# EasyEda_SCH_CAD-Mouse_2025-05-26.net
KiCad netlist of a schematic drawn in EasyEDA
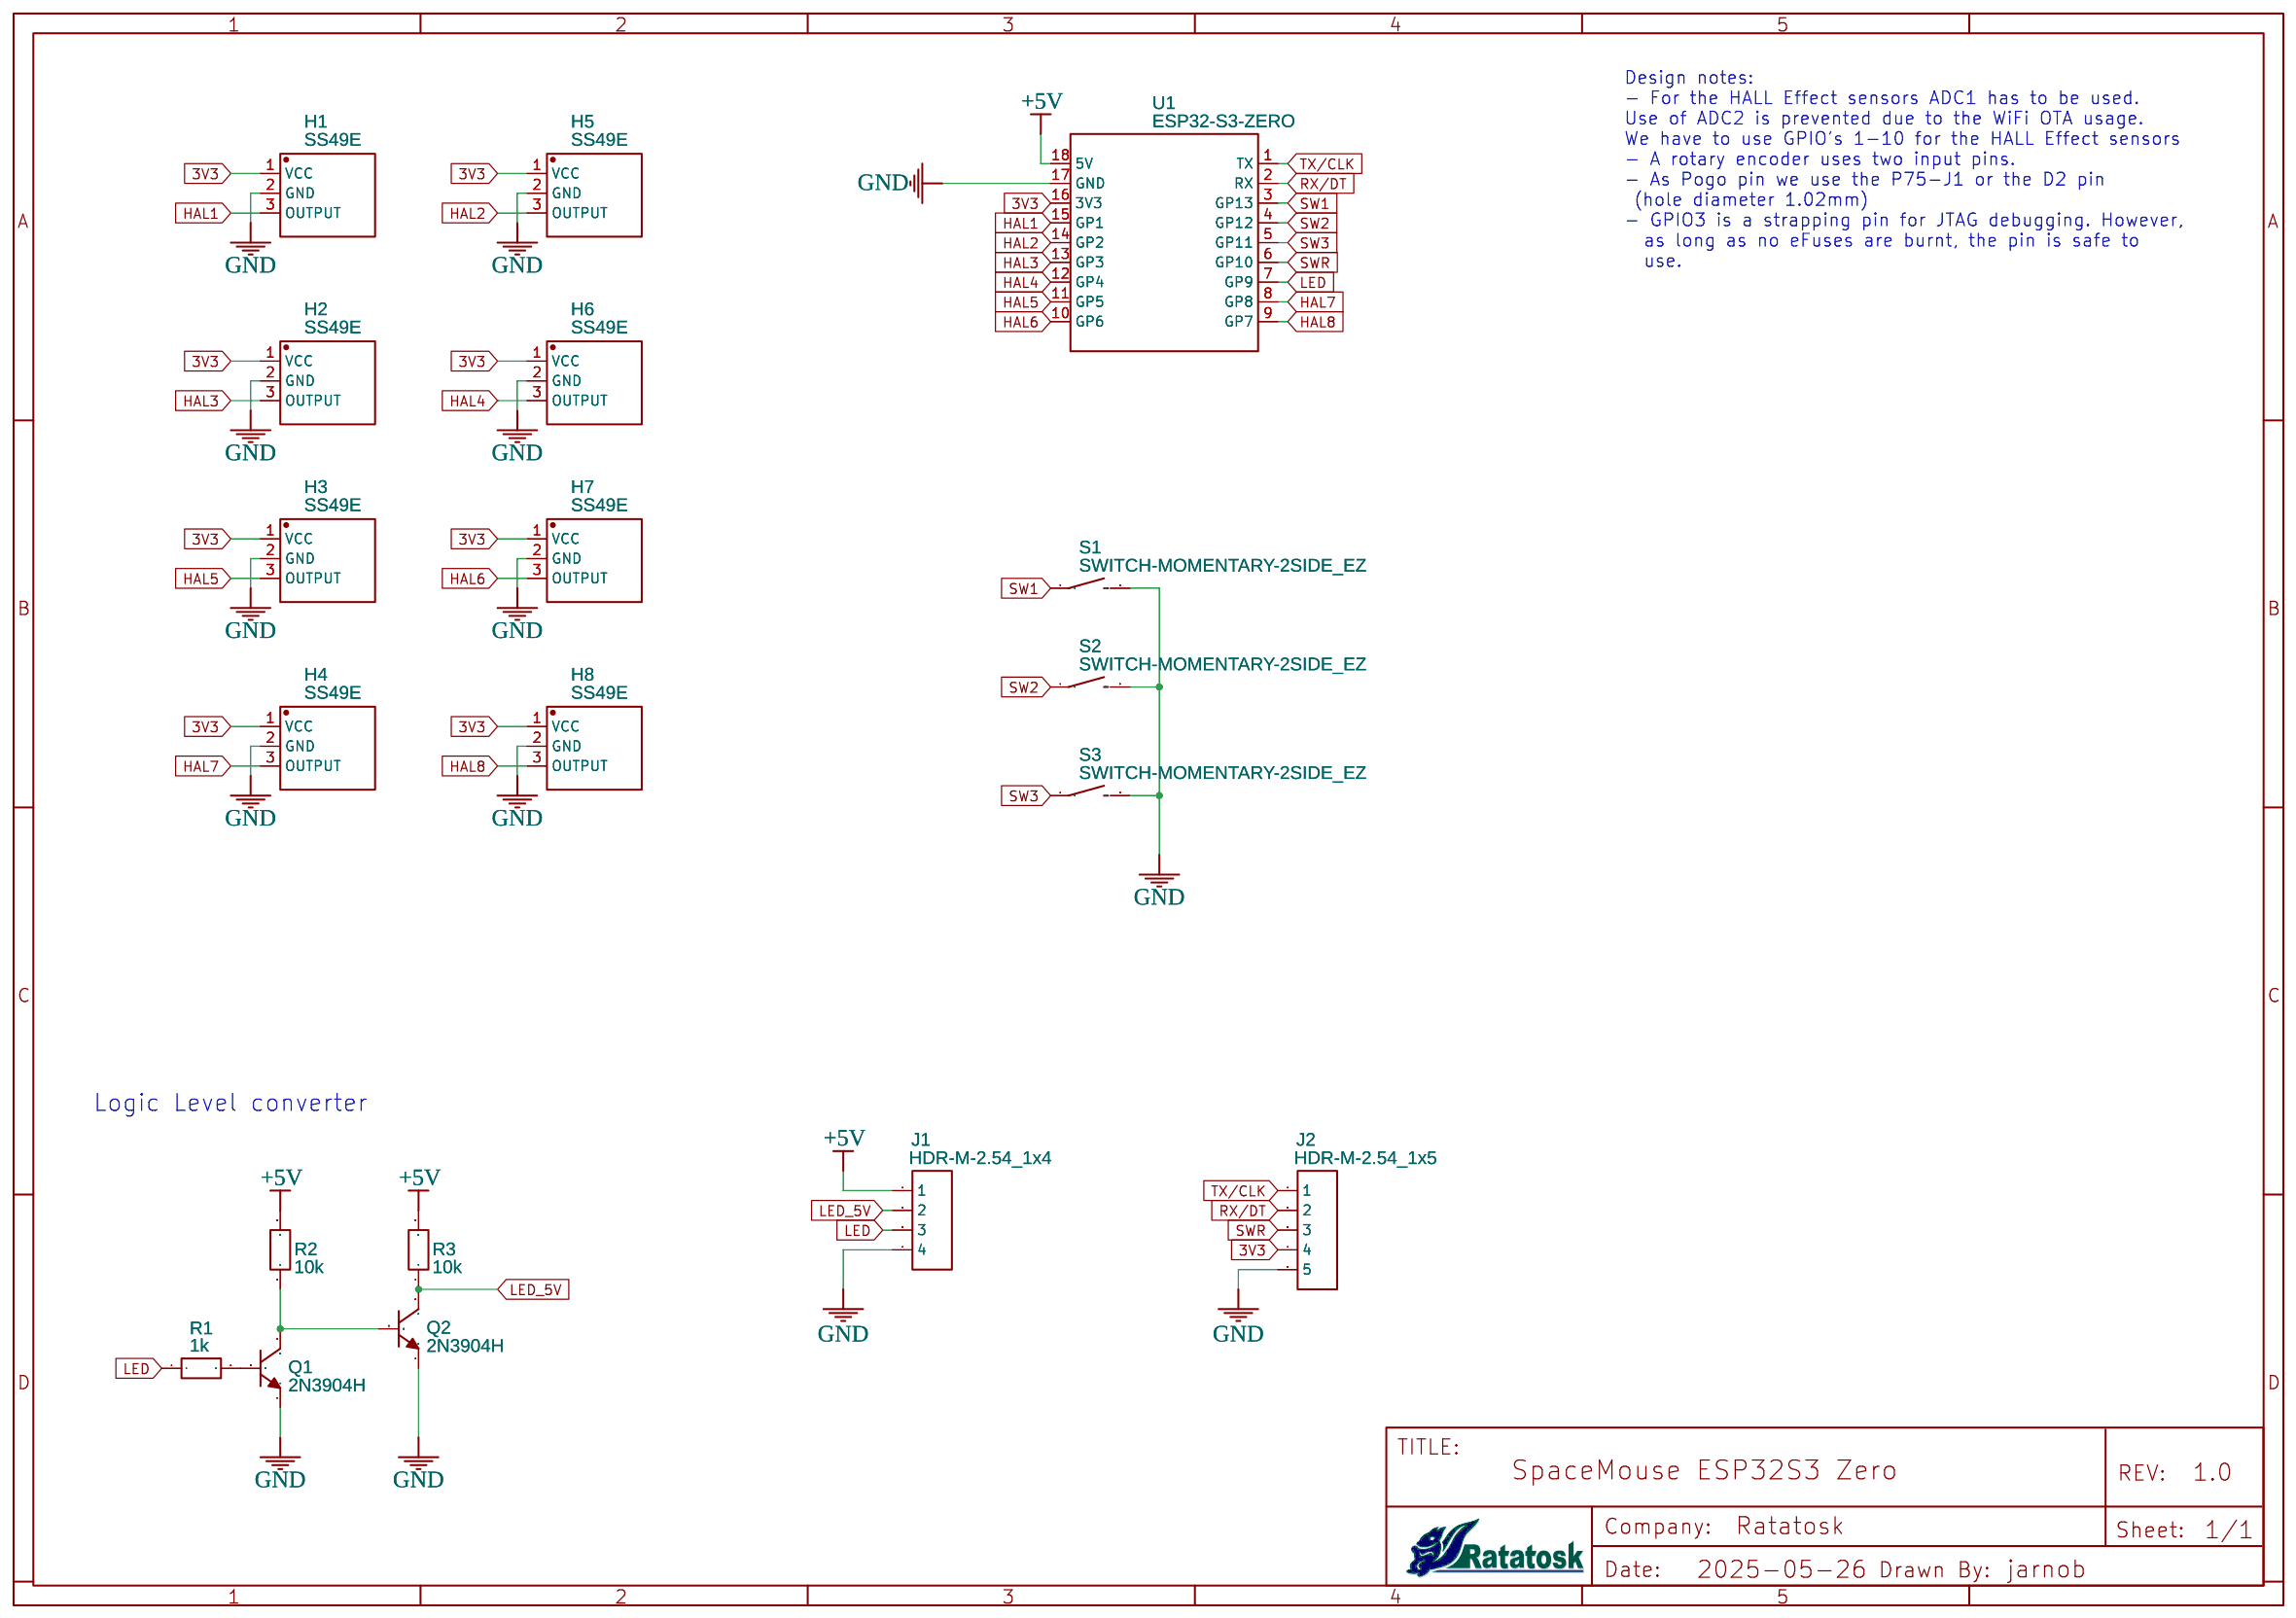
[diagram p0: Schematic]
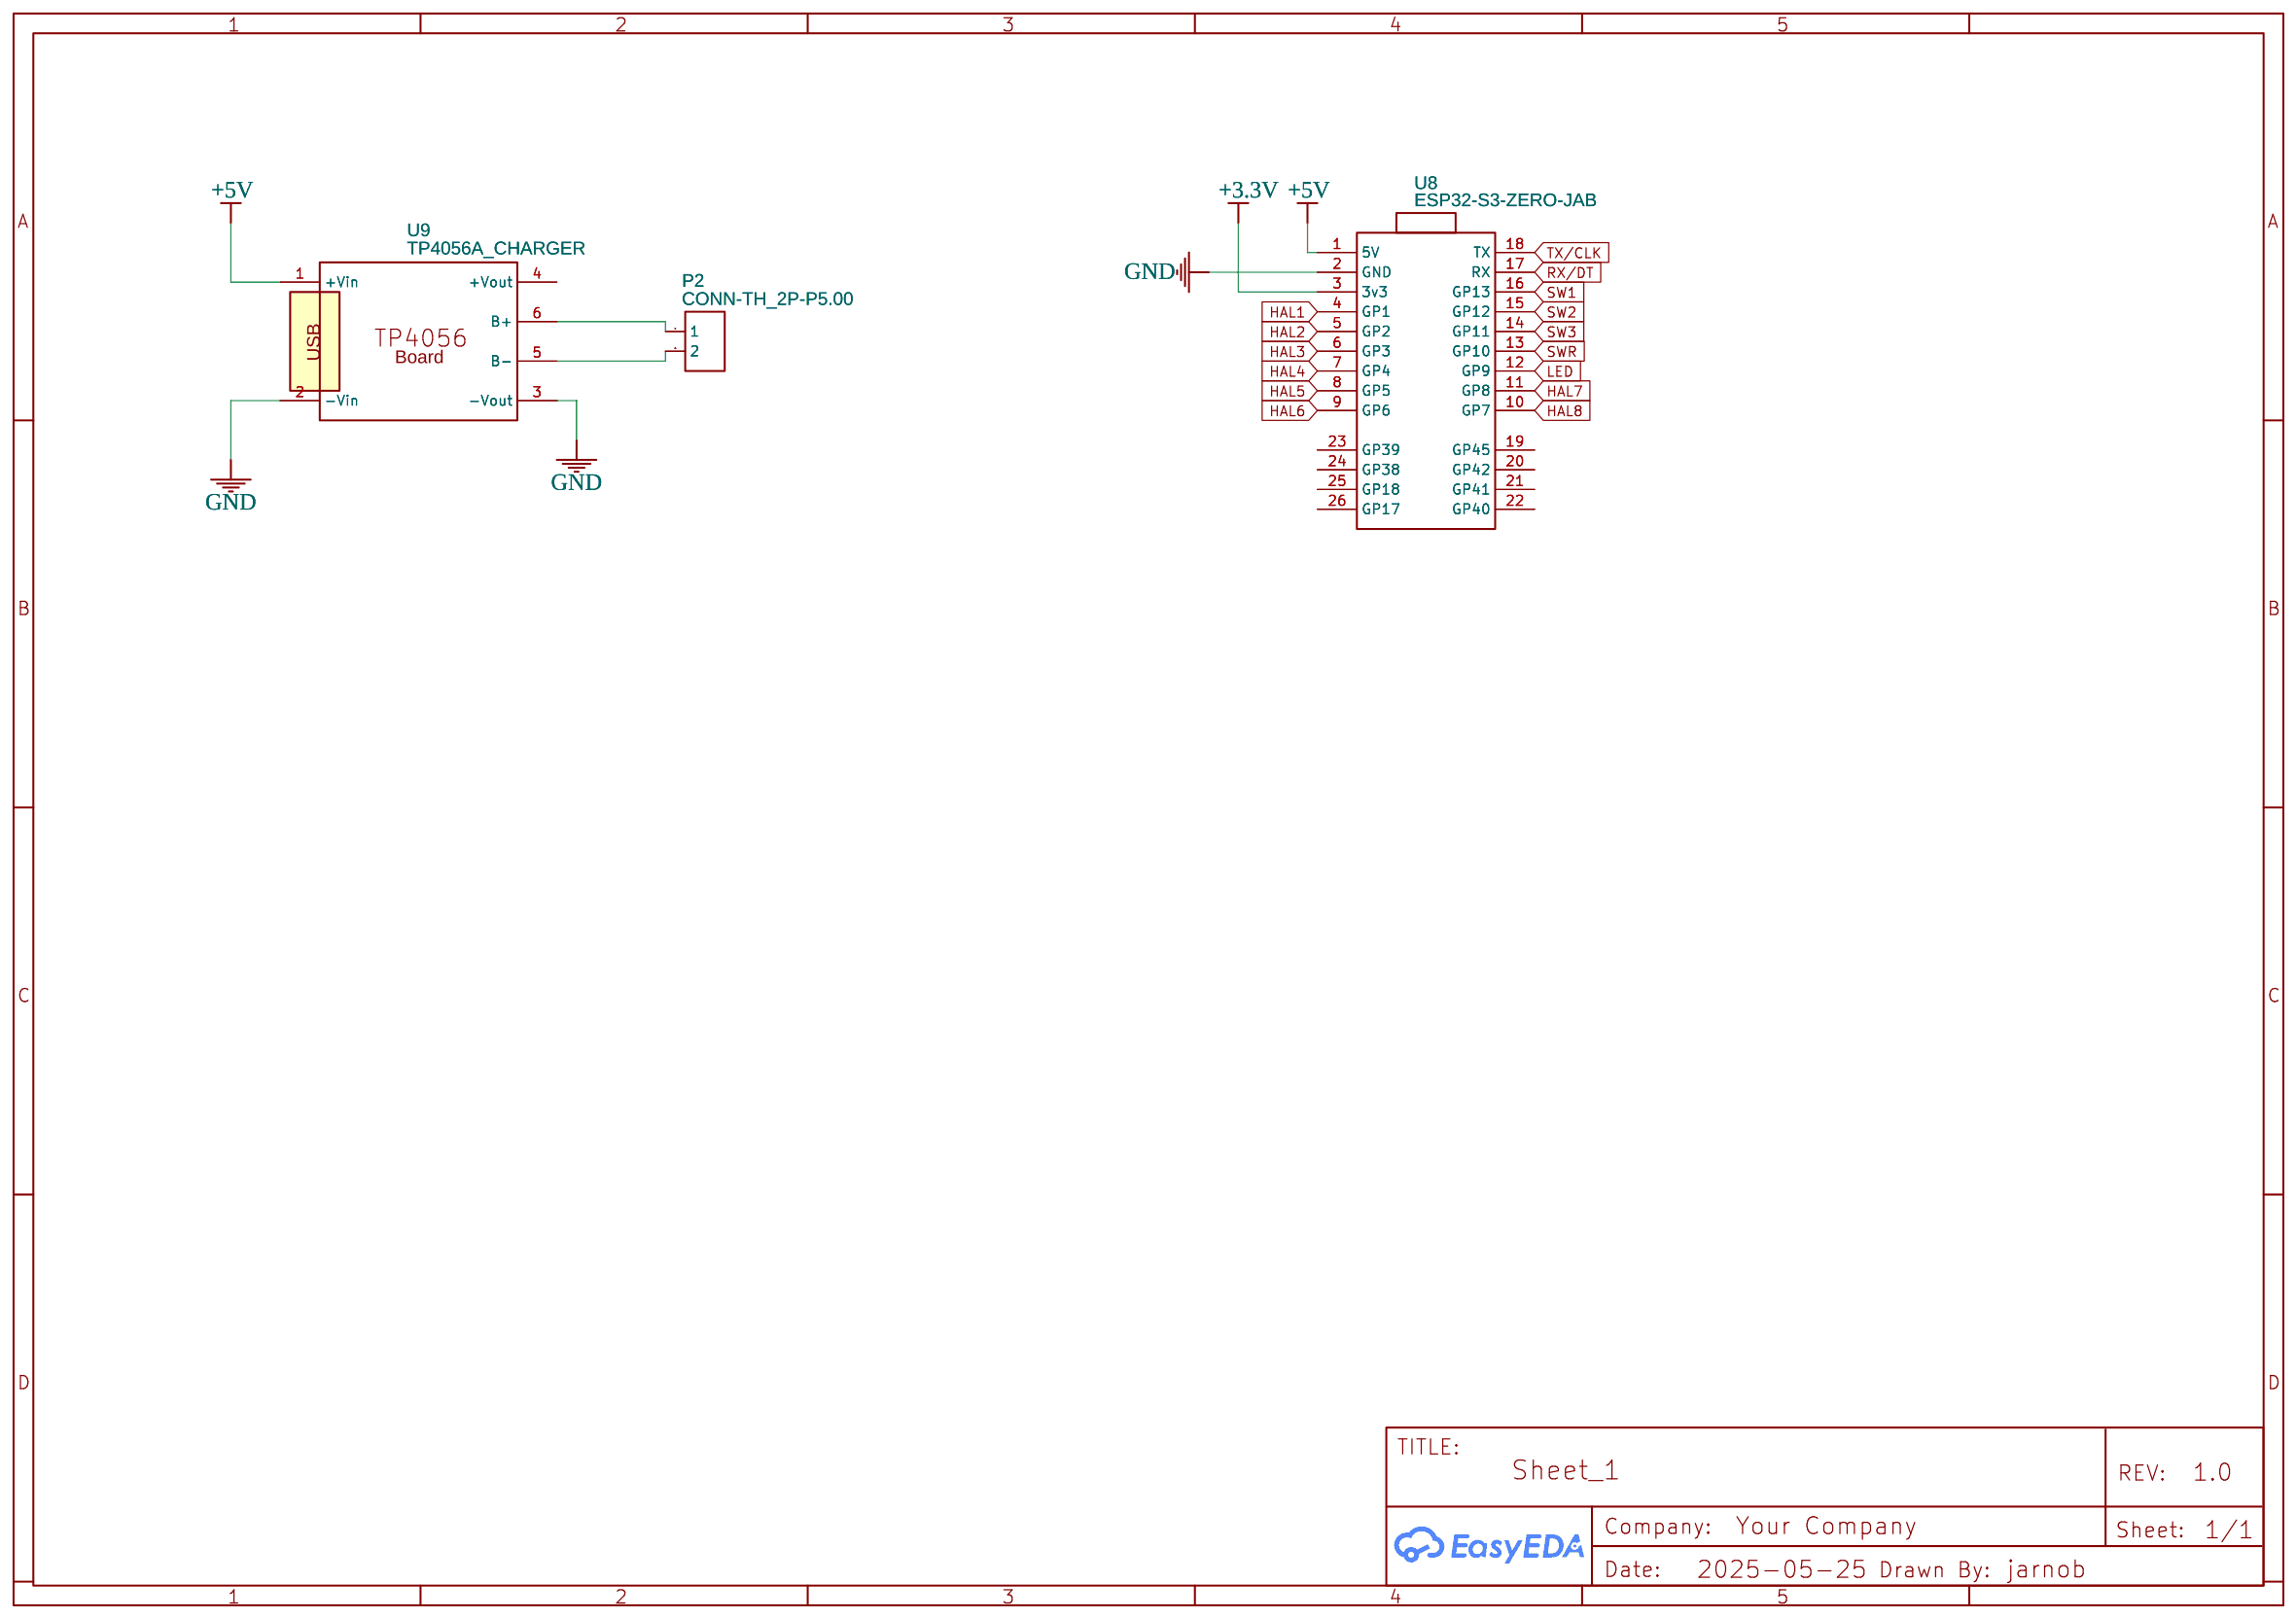
[diagram p1: Components]

(export (version "E")
  (design (tool "Eeschema 10.0.6"))
  (components
    (comp (ref "H1") (value "SS49E") (libsource (lib "") (part "SS49 hall sensor")))
    (comp (ref "H2") (value "SS49E") (libsource (lib "") (part "SS49 hall sensor")))
    (comp (ref "H3") (value "SS49E") (libsource (lib "") (part "SS49 hall sensor")))
    (comp (ref "H4") (value "SS49E") (libsource (lib "") (part "SS49 hall sensor")))
    (comp (ref "H5") (value "SS49E") (libsource (lib "") (part "SS49 hall sensor")))
    (comp (ref "H6") (value "SS49E") (libsource (lib "") (part "SS49 hall sensor")))
    (comp (ref "H7") (value "SS49E") (libsource (lib "") (part "SS49 hall sensor")))
    (comp (ref "H8") (value "SS49E") (libsource (lib "") (part "SS49 hall sensor")))
    (comp (ref "J1") (value "HDR-M-2.54_1x4") (libsource (lib "") (part "HDR-M-2.54_1x4")))
    (comp (ref "J2") (value "HDR-M-2.54_1x5") (libsource (lib "") (part "HDR-M-2.54_1x5")))
    (comp (ref "Q1")
      (value "2N3904H")
      (fields (field (name "Manufacturer") "onsemi(安森美)"))
      (libsource (lib "") (part "2N3904H"))
    )
    (comp (ref "Q2")
      (value "2N3904H")
      (fields (field (name "Manufacturer") "onsemi(安森美)"))
      (libsource (lib "") (part "2N3904H"))
    )
    (comp (ref "R1") (value "1k") (libsource (lib "") (part "R_AXIAL-0.3_EU_1")))
    (comp (ref "R2") (value "10k") (libsource (lib "") (part "R_AXIAL-0.3_EU")))
    (comp (ref "R3") (value "10k") (libsource (lib "") (part "R_AXIAL-0.3_EU")))
    (comp (ref "S1")
      (value "SWITCH-MOMENTARY-2SIDE_EZ")
      (libsource (lib "") (part "SWITCH-MOMENTARY-2SIDE_EZ"))
    )
    (comp (ref "S2")
      (value "SWITCH-MOMENTARY-2SIDE_EZ")
      (libsource (lib "") (part "SWITCH-MOMENTARY-2SIDE_EZ"))
    )
    (comp (ref "S3")
      (value "SWITCH-MOMENTARY-2SIDE_EZ")
      (libsource (lib "") (part "SWITCH-MOMENTARY-2SIDE_EZ"))
    )
    (comp (ref "U1")
      (value "ESP32-S3-ZERO")
      (fields (field (name "Manufacturer Part") "ESP32-S3-Zero") (field (name "Manufacturer") "Waveshare"))
      (libsource (lib "") (part "ESP32-S3-ZERO"))
    )
    (comp (ref "P2") (value "CONN-TH_2P-P5.00") (libsource (lib "") (part "CONN-TH_2P-P5.00")))
    (comp (ref "U8") (value "ESP32-S3-ZERO-JAB") (libsource (lib "") (part "ESP32-S3-ZERO-JAB")))
    (comp (ref "U9")
      (value "TP4056A_CHARGER")
      (fields (field (name "Manufacturer Part") "TP4056A"))
      (libsource (lib "") (part "TP4056A_CHARGER"))
    )
  )
  (nets
    (net (code "1") (name "+3.3V") (class "Default")
      (node (ref "U8") (pin "3") (pinfunction "3v3_3") (pintype "unspecified"))
    )
    (net (code "2") (name "+5V") (class "Default")
      (node (ref "J1") (pin "1") (pinfunction "1_1") (pintype "unspecified"))
      (node (ref "R2") (pin "2") (pinfunction "2_2") (pintype "unspecified"))
      (node (ref "R3") (pin "2") (pinfunction "2_2") (pintype "unspecified"))
      (node (ref "U1") (pin "18") (pinfunction "5V_18") (pintype "unspecified"))
      (node (ref "U8") (pin "1") (pinfunction "5V_1") (pintype "unspecified"))
      (node (ref "U9") (pin "1") (pinfunction "+Vin_1") (pintype "input"))
    )
    (net (code "3") (name "3V3") (class "Default")
      (node (ref "H1") (pin "1") (pinfunction "VCC_1") (pintype "unspecified"))
      (node (ref "H2") (pin "1") (pinfunction "VCC_1") (pintype "unspecified"))
      (node (ref "H3") (pin "1") (pinfunction "VCC_1") (pintype "unspecified"))
      (node (ref "H4") (pin "1") (pinfunction "VCC_1") (pintype "unspecified"))
      (node (ref "H5") (pin "1") (pinfunction "VCC_1") (pintype "unspecified"))
      (node (ref "H6") (pin "1") (pinfunction "VCC_1") (pintype "unspecified"))
      (node (ref "H7") (pin "1") (pinfunction "VCC_1") (pintype "unspecified"))
      (node (ref "H8") (pin "1") (pinfunction "VCC_1") (pintype "unspecified"))
      (node (ref "J2") (pin "4") (pinfunction "4_4") (pintype "unspecified"))
      (node (ref "U1") (pin "16") (pinfunction "3V3_16") (pintype "unspecified"))
    )
    (net (code "4") (name "GND") (class "Default")
      (node (ref "H1") (pin "2") (pinfunction "GND_2") (pintype "unspecified"))
      (node (ref "H2") (pin "2") (pinfunction "GND_2") (pintype "unspecified"))
      (node (ref "H3") (pin "2") (pinfunction "GND_2") (pintype "unspecified"))
      (node (ref "H4") (pin "2") (pinfunction "GND_2") (pintype "unspecified"))
      (node (ref "H5") (pin "2") (pinfunction "GND_2") (pintype "unspecified"))
      (node (ref "H6") (pin "2") (pinfunction "GND_2") (pintype "unspecified"))
      (node (ref "H7") (pin "2") (pinfunction "GND_2") (pintype "unspecified"))
      (node (ref "H8") (pin "2") (pinfunction "GND_2") (pintype "unspecified"))
      (node (ref "J1") (pin "4") (pinfunction "4_4") (pintype "unspecified"))
      (node (ref "J2") (pin "5") (pinfunction "5_5") (pintype "unspecified"))
      (node (ref "Q1") (pin "1") (pinfunction "E_1") (pintype "unspecified"))
      (node (ref "Q2") (pin "1") (pinfunction "E_1") (pintype "unspecified"))
      (node (ref "S1") (pin "2") (pinfunction "2_2") (pintype "bidirectional"))
      (node (ref "S2") (pin "2") (pinfunction "2_2") (pintype "bidirectional"))
      (node (ref "S3") (pin "2") (pinfunction "2_2") (pintype "bidirectional"))
      (node (ref "U1") (pin "17") (pinfunction "GND_17") (pintype "unspecified"))
      (node (ref "U8") (pin "2") (pinfunction "GND_2") (pintype "unspecified"))
      (node (ref "U9") (pin "2") (pinfunction "-Vin_2") (pintype "input"))
      (node (ref "U9") (pin "3") (pinfunction "-Vout_3") (pintype "output"))
    )
    (net (code "5") (name "HAL1") (class "Default")
      (node (ref "H1") (pin "3") (pinfunction "OUTPUT_3") (pintype "unspecified"))
      (node (ref "U1") (pin "15") (pinfunction "GP1_15") (pintype "unspecified"))
      (node (ref "U8") (pin "4") (pinfunction "GP1_4") (pintype "unspecified"))
    )
    (net (code "6") (name "HAL2") (class "Default")
      (node (ref "H5") (pin "3") (pinfunction "OUTPUT_3") (pintype "unspecified"))
      (node (ref "U1") (pin "14") (pinfunction "GP2_14") (pintype "unspecified"))
      (node (ref "U8") (pin "5") (pinfunction "GP2_5") (pintype "unspecified"))
    )
    (net (code "7") (name "HAL3") (class "Default")
      (node (ref "H2") (pin "3") (pinfunction "OUTPUT_3") (pintype "unspecified"))
      (node (ref "U1") (pin "13") (pinfunction "GP3_13") (pintype "unspecified"))
      (node (ref "U8") (pin "6") (pinfunction "GP3_6") (pintype "unspecified"))
    )
    (net (code "8") (name "HAL4") (class "Default")
      (node (ref "H6") (pin "3") (pinfunction "OUTPUT_3") (pintype "unspecified"))
      (node (ref "U1") (pin "12") (pinfunction "GP4_12") (pintype "unspecified"))
      (node (ref "U8") (pin "7") (pinfunction "GP4_7") (pintype "unspecified"))
    )
    (net (code "9") (name "HAL5") (class "Default")
      (node (ref "H3") (pin "3") (pinfunction "OUTPUT_3") (pintype "unspecified"))
      (node (ref "U1") (pin "11") (pinfunction "GP5_11") (pintype "unspecified"))
      (node (ref "U8") (pin "8") (pinfunction "GP5_8") (pintype "unspecified"))
    )
    (net (code "10") (name "HAL6") (class "Default")
      (node (ref "H7") (pin "3") (pinfunction "OUTPUT_3") (pintype "unspecified"))
      (node (ref "U1") (pin "10") (pinfunction "GP6_10") (pintype "unspecified"))
      (node (ref "U8") (pin "9") (pinfunction "GP6_9") (pintype "unspecified"))
    )
    (net (code "11") (name "HAL7") (class "Default")
      (node (ref "H4") (pin "3") (pinfunction "OUTPUT_3") (pintype "unspecified"))
      (node (ref "U1") (pin "8") (pinfunction "GP8_8") (pintype "unspecified"))
      (node (ref "U8") (pin "11") (pinfunction "GP8_11") (pintype "unspecified"))
    )
    (net (code "12") (name "HAL8") (class "Default")
      (node (ref "H8") (pin "3") (pinfunction "OUTPUT_3") (pintype "unspecified"))
      (node (ref "U1") (pin "9") (pinfunction "GP7_9") (pintype "unspecified"))
      (node (ref "U8") (pin "10") (pinfunction "GP7_10") (pintype "unspecified"))
    )
    (net (code "13") (name "LED") (class "Default")
      (node (ref "J1") (pin "3") (pinfunction "3_3") (pintype "unspecified"))
      (node (ref "R1") (pin "1") (pinfunction "1_1") (pintype "unspecified"))
      (node (ref "U1") (pin "7") (pinfunction "GP9_7") (pintype "unspecified"))
      (node (ref "U8") (pin "12") (pinfunction "GP9_12") (pintype "unspecified"))
    )
    (net (code "14") (name "LED_5V") (class "Default")
      (node (ref "J1") (pin "2") (pinfunction "2_2") (pintype "unspecified"))
      (node (ref "Q2") (pin "3") (pinfunction "C_3") (pintype "unspecified"))
      (node (ref "R3") (pin "1") (pinfunction "1_1") (pintype "unspecified"))
    )
    (net (code "15") (name "Net-(Q1-B)") (class "Default")
      (node (ref "Q1") (pin "2") (pinfunction "B_2") (pintype "unspecified"))
      (node (ref "R1") (pin "2") (pinfunction "2_2") (pintype "unspecified"))
    )
    (net (code "16") (name "Net-(Q1-C)") (class "Default")
      (node (ref "Q1") (pin "3") (pinfunction "C_3") (pintype "unspecified"))
      (node (ref "Q2") (pin "2") (pinfunction "B_2") (pintype "unspecified"))
      (node (ref "R2") (pin "1") (pinfunction "1_1") (pintype "unspecified"))
    )
    (net (code "17") (name "Net-(U9-B+)") (class "Default")
      (node (ref "P2") (pin "1") (pinfunction "1_1") (pintype "unspecified"))
      (node (ref "U9") (pin "6") (pinfunction "B+_6") (pintype "input"))
    )
    (net (code "18") (name "Net-(U9-B-)") (class "Default")
      (node (ref "P2") (pin "2") (pinfunction "2_2") (pintype "unspecified"))
      (node (ref "U9") (pin "5") (pinfunction "B-_5") (pintype "input"))
    )
    (net (code "19") (name "RX{slash}DT") (class "Default")
      (node (ref "J2") (pin "2") (pinfunction "2_2") (pintype "unspecified"))
      (node (ref "U1") (pin "2") (pinfunction "RX_2") (pintype "unspecified"))
      (node (ref "U8") (pin "17") (pinfunction "RX_17") (pintype "unspecified"))
    )
    (net (code "20") (name "SW1") (class "Default")
      (node (ref "S1") (pin "1") (pinfunction "1_1") (pintype "bidirectional"))
      (node (ref "U1") (pin "3") (pinfunction "GP13_3") (pintype "unspecified"))
      (node (ref "U8") (pin "16") (pinfunction "GP13_16") (pintype "unspecified"))
    )
    (net (code "21") (name "SW2") (class "Default")
      (node (ref "S2") (pin "1") (pinfunction "1_1") (pintype "bidirectional"))
      (node (ref "U1") (pin "4") (pinfunction "GP12_4") (pintype "unspecified"))
      (node (ref "U8") (pin "15") (pinfunction "GP12_15") (pintype "unspecified"))
    )
    (net (code "22") (name "SW3") (class "Default")
      (node (ref "S3") (pin "1") (pinfunction "1_1") (pintype "bidirectional"))
      (node (ref "U1") (pin "5") (pinfunction "GP11_5") (pintype "unspecified"))
      (node (ref "U8") (pin "14") (pinfunction "GP11_14") (pintype "unspecified"))
    )
    (net (code "23") (name "SWR") (class "Default")
      (node (ref "J2") (pin "3") (pinfunction "3_3") (pintype "unspecified"))
      (node (ref "U1") (pin "6") (pinfunction "GP10_6") (pintype "unspecified"))
      (node (ref "U8") (pin "13") (pinfunction "GP10_13") (pintype "unspecified"))
    )
    (net (code "24") (name "TX{slash}CLK") (class "Default")
      (node (ref "J2") (pin "1") (pinfunction "1_1") (pintype "unspecified"))
      (node (ref "U1") (pin "1") (pinfunction "TX_1") (pintype "unspecified"))
      (node (ref "U8") (pin "18") (pinfunction "TX_18") (pintype "unspecified"))
    )
    (net (code "25") (name "unconnected-(U8-GP17-Pad26)") (class "Default")
      (node (ref "U8") (pin "26") (pinfunction "GP17_26") (pintype "unspecified"))
    )
    (net (code "26") (name "unconnected-(U8-GP18-Pad25)") (class "Default")
      (node (ref "U8") (pin "25") (pinfunction "GP18_25") (pintype "unspecified"))
    )
    (net (code "27") (name "unconnected-(U8-GP38-Pad24)") (class "Default")
      (node (ref "U8") (pin "24") (pinfunction "GP38_24") (pintype "unspecified"))
    )
    (net (code "28") (name "unconnected-(U8-GP39-Pad23)") (class "Default")
      (node (ref "U8") (pin "23") (pinfunction "GP39_23") (pintype "unspecified"))
    )
    (net (code "29") (name "unconnected-(U8-GP40-Pad22)") (class "Default")
      (node (ref "U8") (pin "22") (pinfunction "GP40_22") (pintype "unspecified"))
    )
    (net (code "30") (name "unconnected-(U8-GP41-Pad21)") (class "Default")
      (node (ref "U8") (pin "21") (pinfunction "GP41_21") (pintype "unspecified"))
    )
    (net (code "31") (name "unconnected-(U8-GP42-Pad20)") (class "Default")
      (node (ref "U8") (pin "20") (pinfunction "GP42_20") (pintype "unspecified"))
    )
    (net (code "32") (name "unconnected-(U8-GP45-Pad19)") (class "Default")
      (node (ref "U8") (pin "19") (pinfunction "GP45_19") (pintype "unspecified"))
    )
    (net (code "33") (name "unconnected-(U9-+Vout-Pad4)") (class "Default")
      (node (ref "U9") (pin "4") (pinfunction "+Vout_4") (pintype "output"))
    )
  )
)
